# Ethernet.net
KiCad netlist of a schematic drawn in Altium Designer
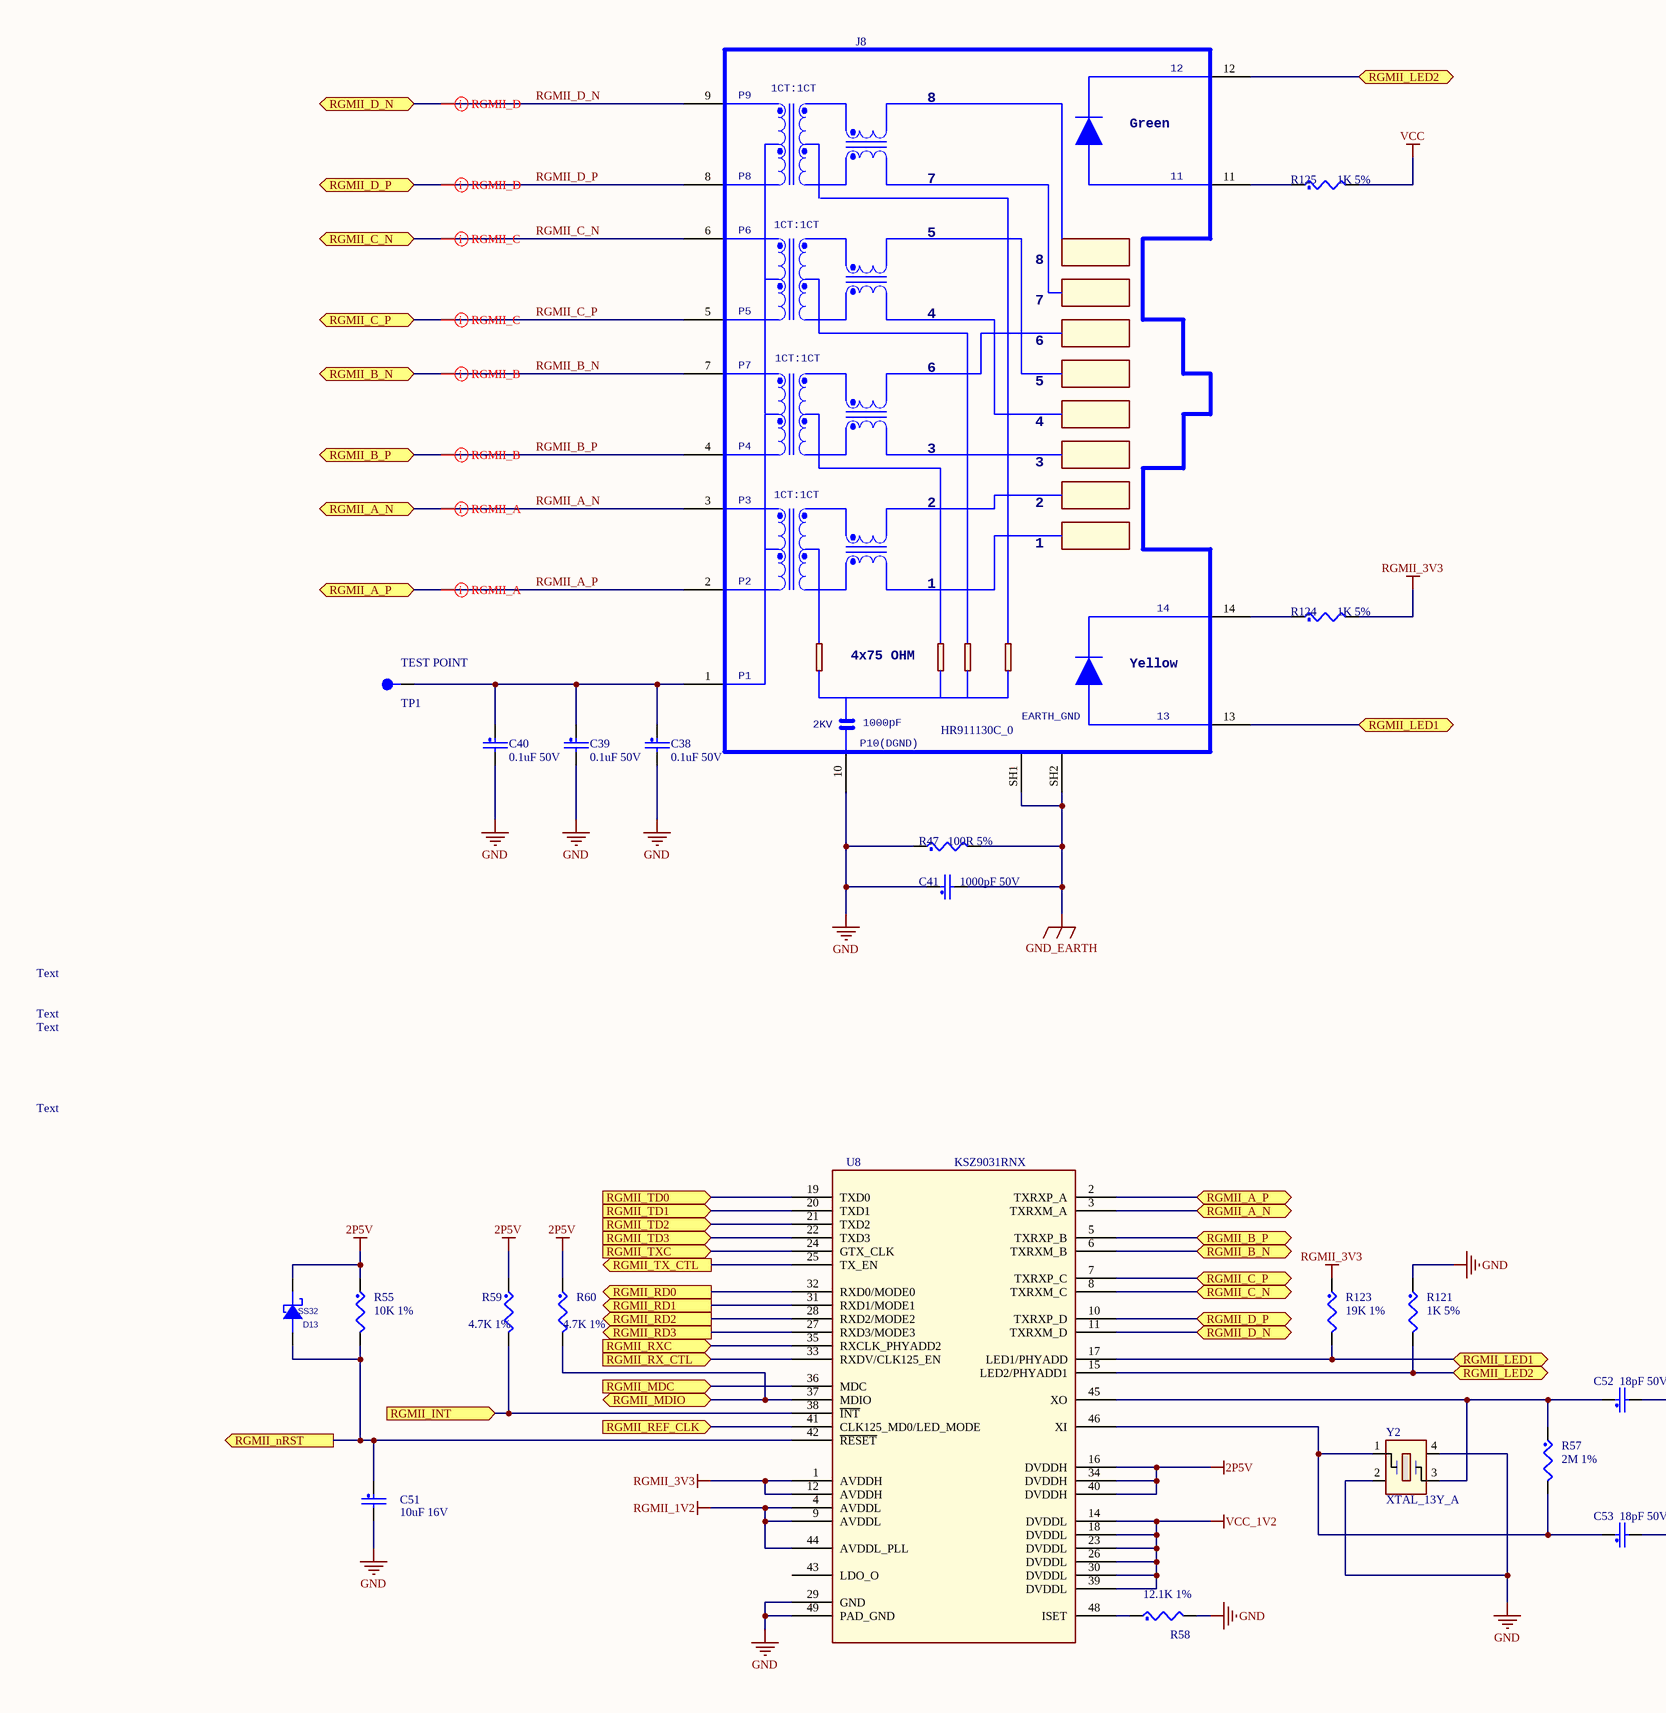
[diagram p0: Ethernet.SchDoc, left]
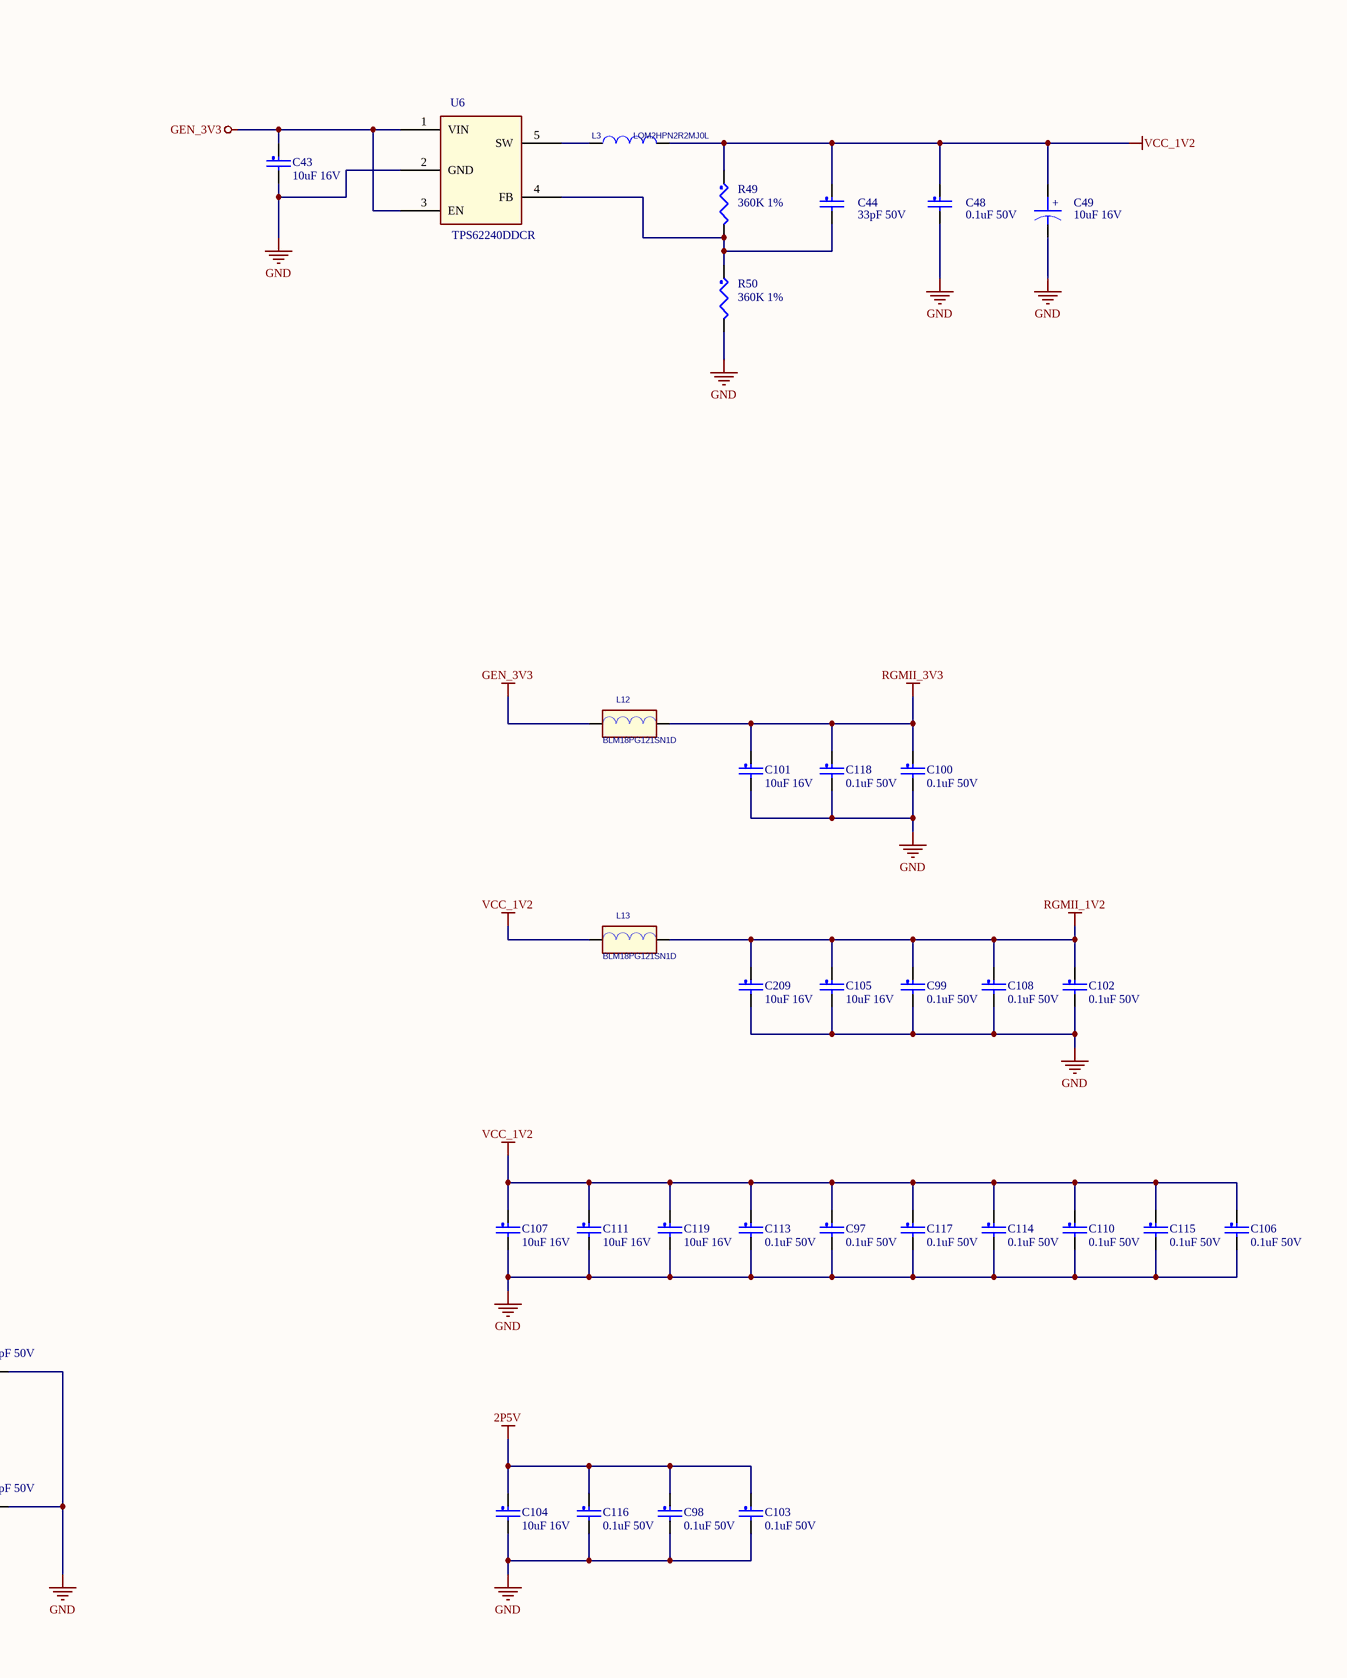
[diagram p1: Ethernet.SchDoc, right]

(export (version "E")
  (design (tool "Eeschema 10.0.6"))
  (components
    (comp (ref "C38")
      (value "0.1uF 50V")
      (footprint "SC0603")
      (libsource (lib "MY-I.MX6-SCH_Library") (part "CAP_NP"))
    )
    (comp (ref "C39")
      (value "0.1uF 50V")
      (footprint "SC0603")
      (libsource (lib "MY-I.MX6-SCH_Library") (part "CAP_NP"))
    )
    (comp (ref "C40")
      (value "0.1uF 50V")
      (footprint "SC0603")
      (libsource (lib "MY-I.MX6-SCH_Library") (part "CAP_NP"))
    )
    (comp (ref "C41")
      (value "1000pF 50V")
      (footprint "SC0603")
      (libsource (lib "MY-I.MX6-SCH_Library") (part "CAP_NP"))
    )
    (comp (ref "C43")
      (value "10uF 16V")
      (footprint "SC0805")
      (libsource (lib "MY-I.MX6-SCH_Library") (part "CAP_NP"))
    )
    (comp (ref "C44")
      (value "33pF 50V")
      (footprint "SC0603")
      (libsource (lib "MY-I.MX6-SCH_Library") (part "CAP_NP"))
    )
    (comp (ref "C48")
      (value "0.1uF 50V")
      (footprint "SC0603")
      (libsource (lib "MY-I.MX6-SCH_Library") (part "CAP_NP"))
    )
    (comp (ref "C49")
      (value "10uF 16V")
      (footprint "SC0805")
      (libsource (lib "MY-I.MX6-SCH_Library") (part "CAPACITOR POL"))
    )
    (comp (ref "C51")
      (value "10uF 16V")
      (footprint "SC0805")
      (libsource (lib "MY-I.MX6-SCH_Library") (part "CAP_NP"))
    )
    (comp (ref "C52")
      (value "18pF 50V")
      (footprint "SC0603")
      (libsource (lib "MY-I.MX6-SCH_Library") (part "CAP_NP"))
    )
    (comp (ref "C53")
      (value "18pF 50V")
      (footprint "SC0603")
      (libsource (lib "MY-I.MX6-SCH_Library") (part "CAP_NP"))
    )
    (comp (ref "C97")
      (value "0.1uF 50V")
      (footprint "SC0603")
      (libsource (lib "MY-I.MX6-SCH_Library") (part "CAP_NP"))
    )
    (comp (ref "C98")
      (value "0.1uF 50V")
      (footprint "SC0603")
      (libsource (lib "MY-I.MX6-SCH_Library") (part "CAP_NP"))
    )
    (comp (ref "C99")
      (value "0.1uF 50V")
      (footprint "SC0603")
      (libsource (lib "MY-I.MX6-SCH_Library") (part "CAP_NP"))
    )
    (comp (ref "C100")
      (value "0.1uF 50V")
      (footprint "SC0603")
      (libsource (lib "MY-I.MX6-SCH_Library") (part "CAP_NP"))
    )
    (comp (ref "C101")
      (value "10uF 16V")
      (footprint "SC0805")
      (libsource (lib "MY-I.MX6-SCH_Library") (part "CAP_NP"))
    )
    (comp (ref "C102")
      (value "0.1uF 50V")
      (footprint "SC0603")
      (libsource (lib "MY-I.MX6-SCH_Library") (part "CAP_NP"))
    )
    (comp (ref "C103")
      (value "0.1uF 50V")
      (footprint "SC0603")
      (libsource (lib "MY-I.MX6-SCH_Library") (part "CAP_NP"))
    )
    (comp (ref "C104")
      (value "10uF 16V")
      (footprint "SC0805")
      (libsource (lib "MY-I.MX6-SCH_Library") (part "CAP_NP"))
    )
    (comp (ref "C105")
      (value "10uF 16V")
      (footprint "SC0805")
      (libsource (lib "MY-I.MX6-SCH_Library") (part "CAP_NP"))
    )
    (comp (ref "C106")
      (value "0.1uF 50V")
      (footprint "SC0603")
      (libsource (lib "MY-I.MX6-SCH_Library") (part "CAP_NP"))
    )
    (comp (ref "C107")
      (value "10uF 16V")
      (footprint "SC0805")
      (libsource (lib "MY-I.MX6-SCH_Library") (part "CAP_NP"))
    )
    (comp (ref "C108")
      (value "0.1uF 50V")
      (footprint "SC0603")
      (libsource (lib "MY-I.MX6-SCH_Library") (part "CAP_NP"))
    )
    (comp (ref "C110")
      (value "0.1uF 50V")
      (footprint "SC0603")
      (libsource (lib "MY-I.MX6-SCH_Library") (part "CAP_NP"))
    )
    (comp (ref "C111")
      (value "10uF 16V")
      (footprint "SC0805")
      (libsource (lib "MY-I.MX6-SCH_Library") (part "CAP_NP"))
    )
    (comp (ref "C113")
      (value "0.1uF 50V")
      (footprint "SC0805")
      (libsource (lib "MY-I.MX6-SCH_Library") (part "CAP_NP"))
    )
    (comp (ref "C114")
      (value "0.1uF 50V")
      (footprint "SC0603")
      (libsource (lib "MY-I.MX6-SCH_Library") (part "CAP_NP"))
    )
    (comp (ref "C115")
      (value "0.1uF 50V")
      (footprint "SC0603")
      (libsource (lib "MY-I.MX6-SCH_Library") (part "CAP_NP"))
    )
    (comp (ref "C116")
      (value "0.1uF 50V")
      (footprint "SC0603")
      (libsource (lib "MY-I.MX6-SCH_Library") (part "CAP_NP"))
    )
    (comp (ref "C117")
      (value "0.1uF 50V")
      (footprint "SC0603")
      (libsource (lib "MY-I.MX6-SCH_Library") (part "CAP_NP"))
    )
    (comp (ref "C118")
      (value "0.1uF 50V")
      (footprint "SC0603")
      (libsource (lib "MY-I.MX6-SCH_Library") (part "CAP_NP"))
    )
    (comp (ref "C119")
      (value "10uF 16V")
      (footprint "SC0805")
      (libsource (lib "MY-I.MX6-SCH_Library") (part "CAP_NP"))
    )
    (comp (ref "C209")
      (value "10uF 16V")
      (footprint "SC0805")
      (libsource (lib "MY-I.MX6-SCH_Library") (part "CAP_NP"))
    )
    (comp (ref "D13")
      (value "SS32")
      (footprint "DO-214AA")
      (libsource (lib "MY-I.MX6-SCH_Library") (part "DIODE SCHOTTKY"))
    )
    (comp (ref "J8")
      (value "HR911130C_0")
      (footprint "RJ45-HANRUN-fixed")
      (libsource (lib "MY-I.MX6-SCH_Library") (part "HR911130C_0"))
    )
    (comp (ref "L3")
      (value "LQM2HPN2R2MJ0L")
      (footprint "SPM2P5X2")
      (libsource (lib "MY-I.MX6-SCH_Library") (part "INDUCTOR"))
    )
    (comp (ref "L12")
      (value "BLM18PG121SN1D")
      (footprint "SFB0603")
      (libsource (lib "MY-I.MX6-SCH_Library") (part "BEAD"))
    )
    (comp (ref "L13")
      (value "BLM18PG121SN1D")
      (footprint "SFB0603")
      (libsource (lib "MY-I.MX6-SCH_Library") (part "BEAD"))
    )
    (comp (ref "R47")
      (value "100R 5%")
      (footprint "SR0603")
      (libsource (lib "MY-I.MX6-SCH_Library") (part "RES"))
    )
    (comp (ref "R49")
      (value "360K 1%")
      (footprint "SR0603")
      (libsource (lib "MY-I.MX6-SCH_Library") (part "RES"))
    )
    (comp (ref "R50")
      (value "360K 1%")
      (footprint "SR0603")
      (libsource (lib "MY-I.MX6-SCH_Library") (part "RES"))
    )
    (comp (ref "R55")
      (value "10K 1%")
      (footprint "SR0603")
      (libsource (lib "MY-I.MX6-SCH_Library") (part "RES"))
    )
    (comp (ref "R57")
      (value "2M 1%")
      (footprint "SR0603")
      (libsource (lib "MY-I.MX6-SCH_Library") (part "RES"))
    )
    (comp (ref "R58")
      (value "12.1K 1%")
      (footprint "SR0603")
      (libsource (lib "MY-I.MX6-SCH_Library") (part "RES"))
    )
    (comp (ref "R59")
      (value "4.7K 1%")
      (footprint "SR0603")
      (libsource (lib "MY-I.MX6-SCH_Library") (part "RES"))
    )
    (comp (ref "R60")
      (value "4.7K 1%")
      (footprint "SR0603")
      (libsource (lib "MY-I.MX6-SCH_Library") (part "RES"))
    )
    (comp (ref "R121")
      (value "1K 5%")
      (footprint "SR0603")
      (libsource (lib "MY-I.MX6-SCH_Library") (part "RES"))
    )
    (comp (ref "R123")
      (value "19K 1%")
      (footprint "SR0603")
      (libsource (lib "MY-I.MX6-SCH_Library") (part "RES"))
    )
    (comp (ref "R124")
      (value "1K 5%")
      (footprint "SR0603")
      (libsource (lib "MY-I.MX6-SCH_Library") (part "RES"))
    )
    (comp (ref "R125")
      (value "1K 5%")
      (footprint "SR0603")
      (libsource (lib "MY-I.MX6-SCH_Library") (part "RES"))
    )
    (comp (ref "TP1")
      (value "TEST POINT")
      (footprint "TP_C")
      (libsource (lib "MY-I.MX6-SCH_Library") (part "TP"))
    )
    (comp (ref "U6")
      (value "TPS62240DDCR")
      (footprint "SOT23-5")
      (libsource (lib "MY-I.MX6-SCH_Library") (part "TPS62240DDCR"))
    )
    (comp (ref "U8")
      (value "KSZ9031RNX")
      (footprint "QFN48-0P5-7X7")
      (libsource (lib "MY-I.MX6-SCH_Library") (part "KSZ9031RNX"))
    )
    (comp (ref "Y2")
      (value "XTAL_13Y_A")
      (footprint "SCRY4-3P2X2P5")
      (libsource (lib "MY-I.MX6-SCH_Library") (part "XTAL_13Y_A"))
    )
  )
  (nets
    (net (code "1") (name "/RGMII_A_N") (class "Default")
      (node (ref "J8") (pin "3") (pinfunction "MDI_0-_3") (pintype "passive"))
      (node (ref "U8") (pin "3") (pinfunction "TXRXM_A_3") (pintype "passive"))
    )
    (net (code "2") (name "/RGMII_A_P") (class "Default")
      (node (ref "J8") (pin "2") (pinfunction "MDI_0+_2") (pintype "passive"))
      (node (ref "U8") (pin "2") (pinfunction "TXRXP_A_2") (pintype "passive"))
    )
    (net (code "3") (name "/RGMII_B_N") (class "Default")
      (node (ref "J8") (pin "7") (pinfunction "MDI_1-_7") (pintype "passive"))
      (node (ref "U8") (pin "6") (pinfunction "TXRXM_B_6") (pintype "passive"))
    )
    (net (code "4") (name "/RGMII_B_P") (class "Default")
      (node (ref "J8") (pin "4") (pinfunction "MDI_1+_4") (pintype "passive"))
      (node (ref "U8") (pin "5") (pinfunction "TXRXP_B_5") (pintype "passive"))
    )
    (net (code "5") (name "/RGMII_C_N") (class "Default")
      (node (ref "J8") (pin "6") (pinfunction "MDI_2-_6") (pintype "passive"))
      (node (ref "U8") (pin "8") (pinfunction "TXRXM_C_8") (pintype "passive"))
    )
    (net (code "6") (name "/RGMII_C_P") (class "Default")
      (node (ref "J8") (pin "5") (pinfunction "MDI_2+_5") (pintype "passive"))
      (node (ref "U8") (pin "7") (pinfunction "TXRXP_C_7") (pintype "passive"))
    )
    (net (code "7") (name "/RGMII_D_N") (class "Default")
      (node (ref "J8") (pin "9") (pinfunction "MDI_3-_9") (pintype "passive"))
      (node (ref "U8") (pin "11") (pinfunction "TXRXM_D_11") (pintype "passive"))
    )
    (net (code "8") (name "/RGMII_D_P") (class "Default")
      (node (ref "J8") (pin "8") (pinfunction "MDI_3+_8") (pintype "passive"))
      (node (ref "U8") (pin "10") (pinfunction "TXRXP_D_10") (pintype "passive"))
    )
    (net (code "9") (name "/RGMII_INT") (class "Default")
      (node (ref "R59") (pin "2") (pinfunction "2_2") (pintype "passive"))
      (node (ref "U8") (pin "38") (pinfunction "~{INT}_38") (pintype "passive"))
    )
    (net (code "10") (name "/RGMII_LED1") (class "Default")
      (node (ref "J8") (pin "13") (pinfunction "Y_LED-_13") (pintype "passive"))
      (node (ref "R123") (pin "2") (pinfunction "2_2") (pintype "passive"))
      (node (ref "U8") (pin "17") (pinfunction "LED1/PHYADD_17") (pintype "passive"))
    )
    (net (code "11") (name "/RGMII_LED2") (class "Default")
      (node (ref "J8") (pin "12") (pinfunction "G_LED-_12") (pintype "passive"))
      (node (ref "R121") (pin "2") (pinfunction "2_2") (pintype "passive"))
      (node (ref "U8") (pin "15") (pinfunction "LED2/PHYADD1_15") (pintype "passive"))
    )
    (net (code "12") (name "/RGMII_MDC") (class "Default")
      (node (ref "U8") (pin "36") (pinfunction "MDC_36") (pintype "passive"))
    )
    (net (code "13") (name "/RGMII_MDIO") (class "Default")
      (node (ref "R60") (pin "2") (pinfunction "2_2") (pintype "passive"))
      (node (ref "U8") (pin "37") (pinfunction "MDIO_37") (pintype "passive"))
    )
    (net (code "14") (name "/RGMII_RD0") (class "Default")
      (node (ref "U8") (pin "32") (pinfunction "RXD0/MODE0_32") (pintype "passive"))
    )
    (net (code "15") (name "/RGMII_RD1") (class "Default")
      (node (ref "U8") (pin "31") (pinfunction "RXD1/MODE1_31") (pintype "passive"))
    )
    (net (code "16") (name "/RGMII_RD2") (class "Default")
      (node (ref "U8") (pin "28") (pinfunction "RXD2/MODE2_28") (pintype "passive"))
    )
    (net (code "17") (name "/RGMII_RD3") (class "Default")
      (node (ref "U8") (pin "27") (pinfunction "RXD3/MODE3_27") (pintype "passive"))
    )
    (net (code "18") (name "/RGMII_REF_CLK") (class "Default")
      (node (ref "U8") (pin "41") (pinfunction "CLK125_MD0/LED_MODE_41") (pintype "passive"))
    )
    (net (code "19") (name "/RGMII_RXC") (class "Default")
      (node (ref "U8") (pin "35") (pinfunction "RXCLK_PHYADD2_35") (pintype "passive"))
    )
    (net (code "20") (name "/RGMII_RX_CTL") (class "Default")
      (node (ref "U8") (pin "33") (pinfunction "RXDV/CLK125_EN_33") (pintype "passive"))
    )
    (net (code "21") (name "/RGMII_TD0") (class "Default")
      (node (ref "U8") (pin "19") (pinfunction "TXD0_19") (pintype "passive"))
    )
    (net (code "22") (name "/RGMII_TD1") (class "Default")
      (node (ref "U8") (pin "20") (pinfunction "TXD1_20") (pintype "passive"))
    )
    (net (code "23") (name "/RGMII_TD2") (class "Default")
      (node (ref "U8") (pin "21") (pinfunction "TXD2_21") (pintype "passive"))
    )
    (net (code "24") (name "/RGMII_TD3") (class "Default")
      (node (ref "U8") (pin "22") (pinfunction "TXD3_22") (pintype "passive"))
    )
    (net (code "25") (name "/RGMII_TXC") (class "Default")
      (node (ref "U8") (pin "24") (pinfunction "GTX_CLK_24") (pintype "passive"))
    )
    (net (code "26") (name "/RGMII_TX_CTL") (class "Default")
      (node (ref "U8") (pin "25") (pinfunction "TX_EN_25") (pintype "passive"))
    )
    (net (code "27") (name "/RGMII_nRST") (class "Default")
      (node (ref "C51") (pin "1") (pinfunction "1_1") (pintype "passive"))
      (node (ref "D13") (pin "1") (pinfunction "ANODE_1") (pintype "passive"))
      (node (ref "R55") (pin "2") (pinfunction "2_2") (pintype "passive"))
      (node (ref "U8") (pin "42") (pinfunction "~{RESET}_42") (pintype "passive"))
    )
    (net (code "28") (name "2P5V") (class "Default")
      (node (ref "C103") (pin "1") (pinfunction "1_1") (pintype "passive"))
      (node (ref "C104") (pin "1") (pinfunction "1_1") (pintype "passive"))
      (node (ref "C116") (pin "1") (pinfunction "1_1") (pintype "passive"))
      (node (ref "C98") (pin "1") (pinfunction "1_1") (pintype "passive"))
      (node (ref "D13") (pin "2") (pinfunction "CATHODE_2") (pintype "passive"))
      (node (ref "R55") (pin "1") (pinfunction "1_1") (pintype "passive"))
      (node (ref "R59") (pin "1") (pinfunction "1_1") (pintype "passive"))
      (node (ref "R60") (pin "1") (pinfunction "1_1") (pintype "passive"))
      (node (ref "U8") (pin "16") (pinfunction "DVDDH_16") (pintype "power_in"))
      (node (ref "U8") (pin "34") (pinfunction "DVDDH_34") (pintype "power_in"))
      (node (ref "U8") (pin "40") (pinfunction "DVDDH_40") (pintype "power_in"))
    )
    (net (code "29") (name "GEN_3V3") (class "Default")
      (node (ref "C43") (pin "1") (pinfunction "1_1") (pintype "passive"))
      (node (ref "L12") (pin "1") (pinfunction "1_1") (pintype "passive"))
      (node (ref "U6") (pin "1") (pinfunction "VIN_1") (pintype "passive"))
      (node (ref "U6") (pin "3") (pinfunction "EN_3") (pintype "passive"))
    )
    (net (code "30") (name "GND") (class "Default")
      (node (ref "C100") (pin "2") (pinfunction "2_2") (pintype "passive"))
      (node (ref "C101") (pin "2") (pinfunction "2_2") (pintype "passive"))
      (node (ref "C102") (pin "2") (pinfunction "2_2") (pintype "passive"))
      (node (ref "C103") (pin "2") (pinfunction "2_2") (pintype "passive"))
      (node (ref "C104") (pin "2") (pinfunction "2_2") (pintype "passive"))
      (node (ref "C105") (pin "2") (pinfunction "2_2") (pintype "passive"))
      (node (ref "C106") (pin "2") (pinfunction "2_2") (pintype "passive"))
      (node (ref "C107") (pin "2") (pinfunction "2_2") (pintype "passive"))
      (node (ref "C108") (pin "2") (pinfunction "2_2") (pintype "passive"))
      (node (ref "C110") (pin "2") (pinfunction "2_2") (pintype "passive"))
      (node (ref "C111") (pin "2") (pinfunction "2_2") (pintype "passive"))
      (node (ref "C113") (pin "2") (pinfunction "2_2") (pintype "passive"))
      (node (ref "C114") (pin "2") (pinfunction "2_2") (pintype "passive"))
      (node (ref "C115") (pin "2") (pinfunction "2_2") (pintype "passive"))
      (node (ref "C116") (pin "2") (pinfunction "2_2") (pintype "passive"))
      (node (ref "C117") (pin "2") (pinfunction "2_2") (pintype "passive"))
      (node (ref "C118") (pin "2") (pinfunction "2_2") (pintype "passive"))
      (node (ref "C119") (pin "2") (pinfunction "2_2") (pintype "passive"))
      (node (ref "C209") (pin "2") (pinfunction "2_2") (pintype "passive"))
      (node (ref "C38") (pin "2") (pinfunction "2_2") (pintype "passive"))
      (node (ref "C39") (pin "2") (pinfunction "2_2") (pintype "passive"))
      (node (ref "C40") (pin "2") (pinfunction "2_2") (pintype "passive"))
      (node (ref "C41") (pin "1") (pinfunction "1_1") (pintype "passive"))
      (node (ref "C43") (pin "2") (pinfunction "2_2") (pintype "passive"))
      (node (ref "C48") (pin "2") (pinfunction "2_2") (pintype "passive"))
      (node (ref "C49") (pin "2") (pinfunction "2_2") (pintype "passive"))
      (node (ref "C51") (pin "2") (pinfunction "2_2") (pintype "passive"))
      (node (ref "C52") (pin "2") (pinfunction "2_2") (pintype "passive"))
      (node (ref "C53") (pin "2") (pinfunction "2_2") (pintype "passive"))
      (node (ref "C97") (pin "2") (pinfunction "2_2") (pintype "passive"))
      (node (ref "C98") (pin "2") (pinfunction "2_2") (pintype "passive"))
      (node (ref "C99") (pin "2") (pinfunction "2_2") (pintype "passive"))
      (node (ref "J8") (pin "10") (pinfunction "GND_10") (pintype "passive"))
      (node (ref "R121") (pin "1") (pinfunction "1_1") (pintype "passive"))
      (node (ref "R47") (pin "1") (pinfunction "1_1") (pintype "passive"))
      (node (ref "R50") (pin "2") (pinfunction "2_2") (pintype "passive"))
      (node (ref "R58") (pin "2") (pinfunction "2_2") (pintype "passive"))
      (node (ref "U6") (pin "2") (pinfunction "GND_2") (pintype "passive"))
      (node (ref "U8") (pin "29") (pinfunction "GND_29") (pintype "power_in"))
      (node (ref "U8") (pin "49") (pinfunction "PAD_GND_49") (pintype "power_in"))
      (node (ref "Y2") (pin "2") (pinfunction "2_2") (pintype "passive"))
      (node (ref "Y2") (pin "4") (pinfunction "4_4") (pintype "passive"))
    )
    (net (code "31") (name "GND_EARTH") (class "Default")
      (node (ref "C41") (pin "2") (pinfunction "2_2") (pintype "passive"))
      (node (ref "J8") (pin "SH1") (pinfunction "SH1_SH1") (pintype "passive"))
      (node (ref "J8") (pin "SH2") (pinfunction "SH2_SH2") (pintype "passive"))
      (node (ref "R47") (pin "2") (pinfunction "2_2") (pintype "passive"))
    )
    (net (code "32") (name "NC") (class "Default")
      (node (ref "U8") (pin "13") (pinfunction "NC_13") (pintype "power_in"))
      (node (ref "U8") (pin "47") (pinfunction "NC_47") (pintype "power_in"))
    )
    (net (code "33") (name "Net-(J8-CT1{slash}2{slash}3{slash}4)") (class "Default")
      (node (ref "C38") (pin "1") (pinfunction "1_1") (pintype "passive"))
      (node (ref "C39") (pin "1") (pinfunction "1_1") (pintype "passive"))
      (node (ref "C40") (pin "1") (pinfunction "1_1") (pintype "passive"))
      (node (ref "J8") (pin "1") (pinfunction "CT1/2/3/4_1") (pintype "passive"))
      (node (ref "TP1") (pin "1") (pinfunction "1_1") (pintype "passive"))
    )
    (net (code "34") (name "Net-(J8-G_LED+)") (class "Default")
      (node (ref "J8") (pin "11") (pinfunction "G_LED+_11") (pintype "passive"))
      (node (ref "R125") (pin "1") (pinfunction "1_1") (pintype "passive"))
    )
    (net (code "35") (name "Net-(J8-Y_LED+)") (class "Default")
      (node (ref "J8") (pin "14") (pinfunction "Y_LED+_14") (pintype "passive"))
      (node (ref "R124") (pin "1") (pinfunction "1_1") (pintype "passive"))
    )
    (net (code "36") (name "Net-(U6-FB)") (class "Default")
      (node (ref "C44") (pin "2") (pinfunction "2_2") (pintype "passive"))
      (node (ref "R49") (pin "2") (pinfunction "2_2") (pintype "passive"))
      (node (ref "R50") (pin "1") (pinfunction "1_1") (pintype "passive"))
      (node (ref "U6") (pin "4") (pinfunction "FB_4") (pintype "passive"))
    )
    (net (code "37") (name "Net-(U6-SW)") (class "Default")
      (node (ref "L3") (pin "1") (pinfunction "1_1") (pintype "passive"))
      (node (ref "U6") (pin "5") (pinfunction "SW_5") (pintype "passive"))
    )
    (net (code "38") (name "Net-(U8-ISET)") (class "Default")
      (node (ref "R58") (pin "1") (pinfunction "1_1") (pintype "passive"))
      (node (ref "U8") (pin "48") (pinfunction "ISET_48") (pintype "passive"))
    )
    (net (code "39") (name "Net-(U8-XI)") (class "Default")
      (node (ref "C53") (pin "1") (pinfunction "1_1") (pintype "passive"))
      (node (ref "R57") (pin "2") (pinfunction "2_2") (pintype "passive"))
      (node (ref "U8") (pin "46") (pinfunction "XI_46") (pintype "passive"))
      (node (ref "Y2") (pin "1") (pinfunction "1_1") (pintype "passive"))
    )
    (net (code "40") (name "Net-(U8-XO)") (class "Default")
      (node (ref "C52") (pin "1") (pinfunction "1_1") (pintype "passive"))
      (node (ref "R57") (pin "1") (pinfunction "1_1") (pintype "passive"))
      (node (ref "U8") (pin "45") (pinfunction "XO_45") (pintype "passive"))
      (node (ref "Y2") (pin "3") (pinfunction "3_3") (pintype "passive"))
    )
    (net (code "41") (name "RGMII_1V2") (class "Default")
      (node (ref "C102") (pin "1") (pinfunction "1_1") (pintype "passive"))
      (node (ref "C105") (pin "1") (pinfunction "1_1") (pintype "passive"))
      (node (ref "C108") (pin "1") (pinfunction "1_1") (pintype "passive"))
      (node (ref "C209") (pin "1") (pinfunction "1_1") (pintype "passive"))
      (node (ref "C99") (pin "1") (pinfunction "1_1") (pintype "passive"))
      (node (ref "L13") (pin "2") (pinfunction "2_2") (pintype "passive"))
      (node (ref "U8") (pin "4") (pinfunction "AVDDL_4") (pintype "power_in"))
      (node (ref "U8") (pin "44") (pinfunction "AVDDL_PLL_44") (pintype "power_in"))
      (node (ref "U8") (pin "9") (pinfunction "AVDDL_9") (pintype "power_in"))
    )
    (net (code "42") (name "RGMII_3V3") (class "Default")
      (node (ref "C100") (pin "1") (pinfunction "1_1") (pintype "passive"))
      (node (ref "C101") (pin "1") (pinfunction "1_1") (pintype "passive"))
      (node (ref "C118") (pin "1") (pinfunction "1_1") (pintype "passive"))
      (node (ref "L12") (pin "2") (pinfunction "2_2") (pintype "passive"))
      (node (ref "R123") (pin "1") (pinfunction "1_1") (pintype "passive"))
      (node (ref "R124") (pin "2") (pinfunction "2_2") (pintype "passive"))
      (node (ref "U8") (pin "1") (pinfunction "AVDDH_1") (pintype "power_in"))
      (node (ref "U8") (pin "12") (pinfunction "AVDDH_12") (pintype "power_in"))
    )
    (net (code "43") (name "VCC") (class "Default")
      (node (ref "R125") (pin "2") (pinfunction "2_2") (pintype "passive"))
    )
    (net (code "44") (name "VCC_1V2") (class "Default")
      (node (ref "C106") (pin "1") (pinfunction "1_1") (pintype "passive"))
      (node (ref "C107") (pin "1") (pinfunction "1_1") (pintype "passive"))
      (node (ref "C110") (pin "1") (pinfunction "1_1") (pintype "passive"))
      (node (ref "C111") (pin "1") (pinfunction "1_1") (pintype "passive"))
      (node (ref "C113") (pin "1") (pinfunction "1_1") (pintype "passive"))
      (node (ref "C114") (pin "1") (pinfunction "1_1") (pintype "passive"))
      (node (ref "C115") (pin "1") (pinfunction "1_1") (pintype "passive"))
      (node (ref "C117") (pin "1") (pinfunction "1_1") (pintype "passive"))
      (node (ref "C119") (pin "1") (pinfunction "1_1") (pintype "passive"))
      (node (ref "C44") (pin "1") (pinfunction "1_1") (pintype "passive"))
      (node (ref "C48") (pin "1") (pinfunction "1_1") (pintype "passive"))
      (node (ref "C49") (pin "1") (pinfunction "1_1") (pintype "passive"))
      (node (ref "C97") (pin "1") (pinfunction "1_1") (pintype "passive"))
      (node (ref "L13") (pin "1") (pinfunction "1_1") (pintype "passive"))
      (node (ref "L3") (pin "2") (pinfunction "2_2") (pintype "passive"))
      (node (ref "R49") (pin "1") (pinfunction "1_1") (pintype "passive"))
      (node (ref "U8") (pin "14") (pinfunction "DVDDL_14") (pintype "power_in"))
      (node (ref "U8") (pin "18") (pinfunction "DVDDL_18") (pintype "power_in"))
      (node (ref "U8") (pin "23") (pinfunction "DVDDL_23") (pintype "power_in"))
      (node (ref "U8") (pin "26") (pinfunction "DVDDL_26") (pintype "power_in"))
      (node (ref "U8") (pin "30") (pinfunction "DVDDL_30") (pintype "power_in"))
      (node (ref "U8") (pin "39") (pinfunction "DVDDL_39") (pintype "power_in"))
    )
    (net (code "45") (name "unconnected-(U8-LDO_O-Pad43)") (class "Default")
      (node (ref "U8") (pin "43") (pinfunction "LDO_O_43") (pintype "power_in"))
    )
  )
)
